# SCH.net
KiCad netlist of a schematic drawn in EasyEDA
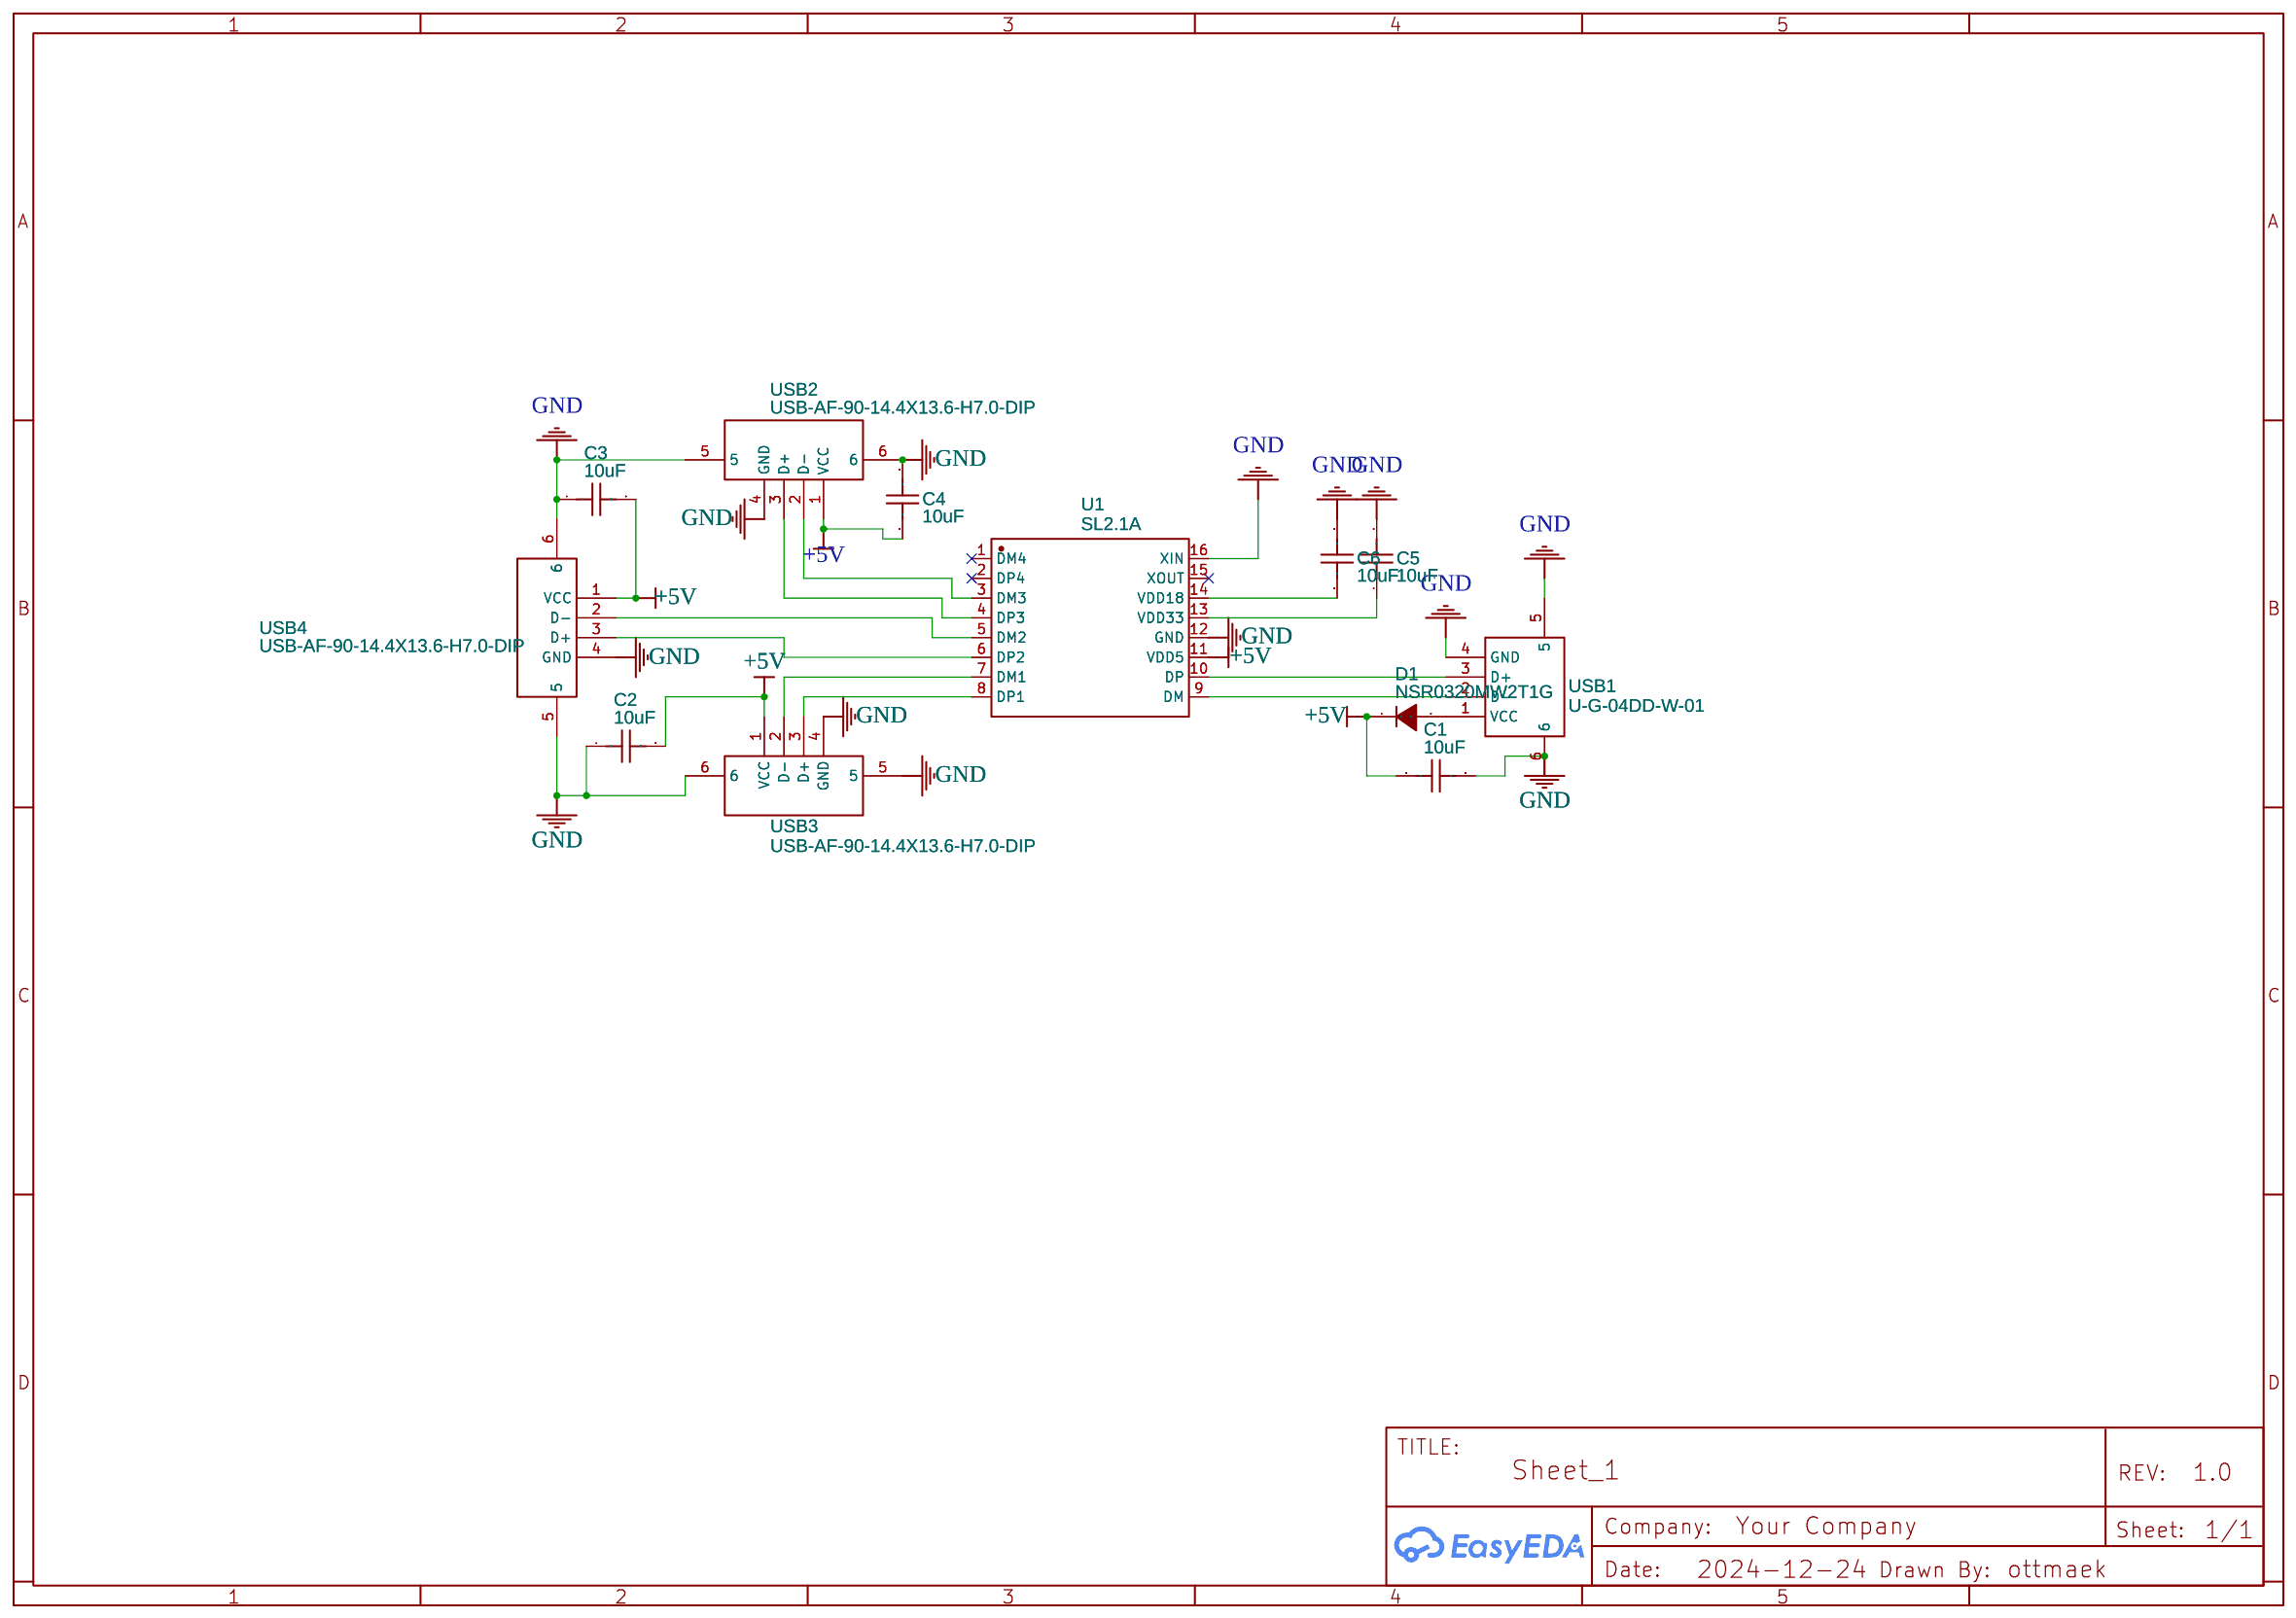
[diagram p0: schematic sheet]

(export (version "E")
  (design (tool "Eeschema 10.0.6"))
  (components
    (comp (ref "C1")
      (value "10uF")
      (fields
        (field (name "Manufacturer Part") "CL10A106KP8NNNC")
        (field (name "Manufacturer") "SAMSUNG(三星)")
      )
      (libsource (lib "") (part "CL10A106KP8NNNC_1"))
    )
    (comp (ref "C2")
      (value "10uF")
      (fields
        (field (name "Manufacturer Part") "CL10A106KP8NNNC")
        (field (name "Manufacturer") "SAMSUNG(三星)")
      )
      (libsource (lib "") (part "CL10A106KP8NNNC_1"))
    )
    (comp (ref "C3")
      (value "10uF")
      (fields
        (field (name "Manufacturer Part") "CL10A106KP8NNNC")
        (field (name "Manufacturer") "SAMSUNG(三星)")
      )
      (libsource (lib "") (part "CL10A106KP8NNNC_1"))
    )
    (comp (ref "C4")
      (value "10uF")
      (fields
        (field (name "Manufacturer Part") "CL10A106KP8NNNC")
        (field (name "Manufacturer") "SAMSUNG(三星)")
      )
      (libsource (lib "") (part "CL10A106KP8NNNC"))
    )
    (comp (ref "C5")
      (value "10uF")
      (fields
        (field (name "Manufacturer Part") "CL10A106KP8NNNC")
        (field (name "Manufacturer") "SAMSUNG(三星)")
      )
      (libsource (lib "") (part "CL10A106KP8NNNC"))
    )
    (comp (ref "C6")
      (value "10uF")
      (fields
        (field (name "Manufacturer Part") "CL10A106KP8NNNC")
        (field (name "Manufacturer") "SAMSUNG(三星)")
      )
      (libsource (lib "") (part "CL10A106KP8NNNC"))
    )
    (comp (ref "D1")
      (value "NSR0320MW2T1G")
      (fields (field (name "Manufacturer") "onsemi(安森美)"))
      (libsource (lib "") (part "NSR0320MW2T1G"))
    )
    (comp (ref "U1")
      (value "SL2.1A")
      (fields (field (name "Manufacturer") "CoreChips(和芯润德)"))
      (libsource (lib "") (part "SL2.1A"))
    )
    (comp (ref "USB1")
      (value "U-G-04DD-W-01")
      (fields (field (name "Manufacturer Part") "U-G-O4DD-W-1") (field (name "Manufacturer") "韩国韩荣"))
      (libsource (lib "") (part "U-G-04DD-W-01"))
    )
    (comp (ref "USB2")
      (value "USB-AF-90-14.4X13.6-H7.0-DIP")
      (fields (field (name "Manufacturer Part") "903-131A1011D10100") (field (name "Manufacturer") "精拓金"))
      (libsource (lib "") (part "USB-AF-90-14.4X13.6-H7.0-DIP"))
    )
    (comp (ref "USB3")
      (value "USB-AF-90-14.4X13.6-H7.0-DIP")
      (fields (field (name "Manufacturer Part") "903-131A1011D10100") (field (name "Manufacturer") "精拓金"))
      (libsource (lib "") (part "USB-AF-90-14.4X13.6-H7.0-DIP_2"))
    )
    (comp (ref "USB4")
      (value "USB-AF-90-14.4X13.6-H7.0-DIP")
      (fields (field (name "Manufacturer Part") "903-131A1011D10100") (field (name "Manufacturer") "精拓金"))
      (libsource (lib "") (part "USB-AF-90-14.4X13.6-H7.0-DIP_1"))
    )
  )
  (nets
    (net (code "1") (name "+5V") (class "Default")
      (node (ref "C1") (pin "1") (pinfunction "1_1") (pintype "unspecified"))
      (node (ref "C2") (pin "2") (pinfunction "2_2") (pintype "unspecified"))
      (node (ref "C3") (pin "2") (pinfunction "2_2") (pintype "unspecified"))
      (node (ref "C4") (pin "1") (pinfunction "1_1") (pintype "unspecified"))
      (node (ref "D1") (pin "1") (pinfunction "C_1") (pintype "unspecified"))
      (node (ref "U1") (pin "11") (pinfunction "VDD5_11") (pintype "unspecified"))
      (node (ref "USB2") (pin "1") (pinfunction "VCC_1") (pintype "unspecified"))
      (node (ref "USB3") (pin "1") (pinfunction "VCC_1") (pintype "unspecified"))
      (node (ref "USB4") (pin "1") (pinfunction "VCC_1") (pintype "unspecified"))
    )
    (net (code "2") (name "GND") (class "Default")
      (node (ref "C1") (pin "2") (pinfunction "2_2") (pintype "unspecified"))
      (node (ref "C2") (pin "1") (pinfunction "1_1") (pintype "unspecified"))
      (node (ref "C3") (pin "1") (pinfunction "1_1") (pintype "unspecified"))
      (node (ref "C4") (pin "2") (pinfunction "2_2") (pintype "unspecified"))
      (node (ref "C5") (pin "2") (pinfunction "2_2") (pintype "unspecified"))
      (node (ref "C6") (pin "2") (pinfunction "2_2") (pintype "unspecified"))
      (node (ref "U1") (pin "12") (pinfunction "GND_12") (pintype "unspecified"))
      (node (ref "U1") (pin "16") (pinfunction "XIN_16") (pintype "unspecified"))
      (node (ref "USB1") (pin "4") (pinfunction "GND_4") (pintype "unspecified"))
      (node (ref "USB1") (pin "5") (pinfunction "5_5") (pintype "unspecified"))
      (node (ref "USB1") (pin "6") (pinfunction "6_6") (pintype "unspecified"))
      (node (ref "USB2") (pin "4") (pinfunction "GND_4") (pintype "unspecified"))
      (node (ref "USB2") (pin "5") (pinfunction "5_5") (pintype "unspecified"))
      (node (ref "USB2") (pin "6") (pinfunction "6_6") (pintype "unspecified"))
      (node (ref "USB3") (pin "4") (pinfunction "GND_4") (pintype "unspecified"))
      (node (ref "USB3") (pin "5") (pinfunction "5_5") (pintype "unspecified"))
      (node (ref "USB3") (pin "6") (pinfunction "6_6") (pintype "unspecified"))
      (node (ref "USB4") (pin "4") (pinfunction "GND_4") (pintype "unspecified"))
      (node (ref "USB4") (pin "5") (pinfunction "5_5") (pintype "unspecified"))
      (node (ref "USB4") (pin "6") (pinfunction "6_6") (pintype "unspecified"))
    )
    (net (code "3") (name "Net-(D1-A)") (class "Default")
      (node (ref "D1") (pin "2") (pinfunction "A_2") (pintype "unspecified"))
      (node (ref "USB1") (pin "1") (pinfunction "VCC_1") (pintype "unspecified"))
    )
    (net (code "4") (name "Net-(U1-DM)") (class "Default")
      (node (ref "U1") (pin "9") (pinfunction "DM_9") (pintype "unspecified"))
      (node (ref "USB1") (pin "2") (pinfunction "D-_2") (pintype "unspecified"))
    )
    (net (code "5") (name "Net-(U1-DM1)") (class "Default")
      (node (ref "U1") (pin "7") (pinfunction "DM1_7") (pintype "unspecified"))
      (node (ref "USB3") (pin "2") (pinfunction "D-_2") (pintype "unspecified"))
    )
    (net (code "6") (name "Net-(U1-DM2)") (class "Default")
      (node (ref "U1") (pin "5") (pinfunction "DM2_5") (pintype "unspecified"))
      (node (ref "USB4") (pin "2") (pinfunction "D-_2") (pintype "unspecified"))
    )
    (net (code "7") (name "Net-(U1-DM3)") (class "Default")
      (node (ref "U1") (pin "3") (pinfunction "DM3_3") (pintype "unspecified"))
      (node (ref "USB2") (pin "2") (pinfunction "D-_2") (pintype "unspecified"))
    )
    (net (code "8") (name "Net-(U1-DP)") (class "Default")
      (node (ref "U1") (pin "10") (pinfunction "DP_10") (pintype "unspecified"))
      (node (ref "USB1") (pin "3") (pinfunction "D+_3") (pintype "unspecified"))
    )
    (net (code "9") (name "Net-(U1-DP1)") (class "Default")
      (node (ref "U1") (pin "8") (pinfunction "DP1_8") (pintype "unspecified"))
      (node (ref "USB3") (pin "3") (pinfunction "D+_3") (pintype "unspecified"))
    )
    (net (code "10") (name "Net-(U1-DP2)") (class "Default")
      (node (ref "U1") (pin "6") (pinfunction "DP2_6") (pintype "unspecified"))
      (node (ref "USB4") (pin "3") (pinfunction "D+_3") (pintype "unspecified"))
    )
    (net (code "11") (name "Net-(U1-DP3)") (class "Default")
      (node (ref "U1") (pin "4") (pinfunction "DP3_4") (pintype "unspecified"))
      (node (ref "USB2") (pin "3") (pinfunction "D+_3") (pintype "unspecified"))
    )
    (net (code "12") (name "Net-(U1-VDD18)") (class "Default")
      (node (ref "C6") (pin "1") (pinfunction "1_1") (pintype "unspecified"))
      (node (ref "U1") (pin "14") (pinfunction "VDD18_14") (pintype "unspecified"))
    )
    (net (code "13") (name "Net-(U1-VDD33)") (class "Default")
      (node (ref "C5") (pin "1") (pinfunction "1_1") (pintype "unspecified"))
      (node (ref "U1") (pin "13") (pinfunction "VDD33_13") (pintype "unspecified"))
    )
    (net (code "14") (name "unconnected-(U1-DM4-Pad1)") (class "Default")
      (node (ref "U1") (pin "1") (pinfunction "DM4_1") (pintype "unspecified+no_connect"))
    )
    (net (code "15") (name "unconnected-(U1-DP4-Pad2)") (class "Default")
      (node (ref "U1") (pin "2") (pinfunction "DP4_2") (pintype "unspecified+no_connect"))
    )
    (net (code "16") (name "unconnected-(U1-XOUT-Pad15)") (class "Default")
      (node (ref "U1") (pin "15") (pinfunction "XOUT_15") (pintype "unspecified+no_connect"))
    )
  )
)
